# Zoom_camera.net
KiCad netlist of a schematic drawn in Altium Designer
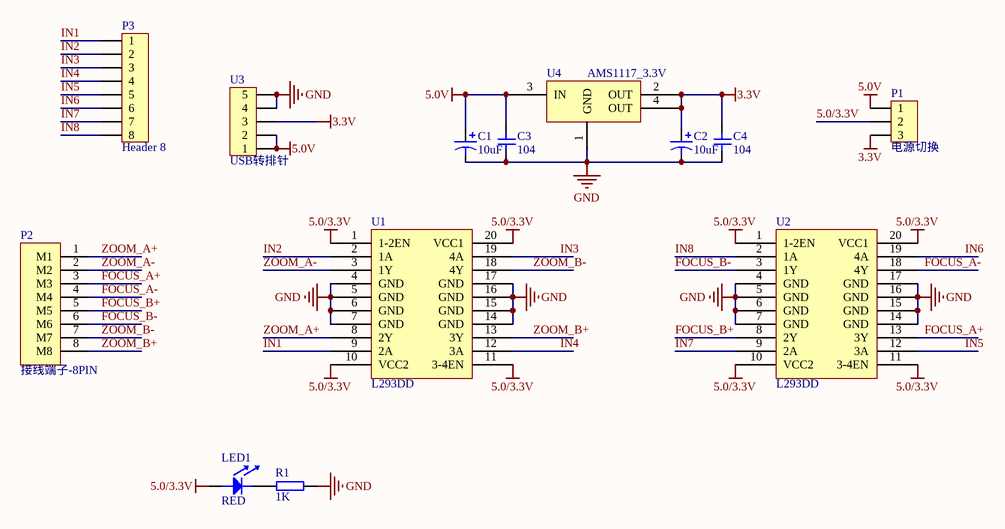
[diagram p0: Zoom_camera.SchDoc]

(export (version "E")
  (design (tool "Eeschema 10.0.6"))
  (components
    (comp (ref "C1")
      (value "10uF")
      (footprint "TAJ-B")
      (description "极性贴片电容")
      (libsource (lib "集大电协1.1.0") (part "Pol Cap"))
    )
    (comp (ref "C2")
      (value "10uF")
      (footprint "TAJ-B")
      (description "极性贴片电容")
      (libsource (lib "集大电协1.1.0") (part "Pol Cap"))
    )
    (comp (ref "C3")
      (value "104")
      (footprint "0805C")
      (description "无极贴片电容")
      (libsource (lib "集大电协1.1.0") (part "Cap1"))
    )
    (comp (ref "C4")
      (value "104")
      (footprint "0805C")
      (description "无极贴片电容")
      (libsource (lib "集大电协1.1.0") (part "Cap1"))
    )
    (comp (ref "LED1")
      (value "RED")
      (footprint "0805LED")
      (description "发光二极管")
      (libsource (lib "集大电协1.1.2") (part "LED"))
    )
    (comp (ref "P1")
      (value "电源切换")
      (footprint "Header 3")
      (description "排针")
      (libsource (lib "集大电协1.1.0") (part "Header 3"))
    )
    (comp (ref "P2")
      (value "接线端子-8PIN")
      (footprint "MX1.25MM-8P")
      (libsource (lib "集大电协1.1.0") (part "接线端子-8PIN"))
    )
    (comp (ref "P3")
      (value "Header 8")
      (footprint "Header 8")
      (description "排针")
      (libsource (lib "集大电协1.1.0") (part "Header 8"))
    )
    (comp (ref "R1")
      (value "1K")
      (footprint "0805R")
      (description "电阻")
      (libsource (lib "集大电协1.1.2") (part "Res"))
    )
    (comp (ref "U1") (value "L293DD") (footprint "SOP-20M") (libsource (lib "集大电协1.1.2") (part "L293D")))
    (comp (ref "U2") (value "L293DD") (footprint "SOP-20M") (libsource (lib "集大电协1.1.2") (part "L293D")))
    (comp (ref "U3") (value "USB转排针") (footprint "USB转排针") (libsource (lib "集大电协1.1.0") (part "USB转排针")))
    (comp (ref "U4")
      (value "AMS1117_3.3V")
      (footprint "SOT-223")
      (description "电源芯片")
      (libsource (lib "集大电协1.1.0") (part "AMS1117-3.3V/5.0V"))
    )
  )
  (nets
    (net (code "1") (name "/FOCUS_A+") (class "Default")
      (node (ref "P2") (pin "3") (pinfunction "M3_3") (pintype "passive"))
      (node (ref "U2") (pin "13") (pinfunction "3Y_13") (pintype "passive"))
    )
    (net (code "2") (name "/FOCUS_A-") (class "Default")
      (node (ref "P2") (pin "4") (pinfunction "M4_4") (pintype "passive"))
      (node (ref "U2") (pin "18") (pinfunction "4Y_18") (pintype "passive"))
    )
    (net (code "3") (name "/FOCUS_B+") (class "Default")
      (node (ref "P2") (pin "5") (pinfunction "M5_5") (pintype "passive"))
      (node (ref "U2") (pin "8") (pinfunction "2Y_8") (pintype "passive"))
    )
    (net (code "4") (name "/FOCUS_B-") (class "Default")
      (node (ref "P2") (pin "6") (pinfunction "M6_6") (pintype "passive"))
      (node (ref "U2") (pin "3") (pinfunction "1Y_3") (pintype "passive"))
    )
    (net (code "5") (name "/IN1") (class "Default")
      (node (ref "P3") (pin "1") (pinfunction "1_1") (pintype "passive"))
      (node (ref "U1") (pin "9") (pinfunction "2A_9") (pintype "passive"))
    )
    (net (code "6") (name "/IN2") (class "Default")
      (node (ref "P3") (pin "2") (pinfunction "2_2") (pintype "passive"))
      (node (ref "U1") (pin "2") (pinfunction "1A_2") (pintype "passive"))
    )
    (net (code "7") (name "/IN3") (class "Default")
      (node (ref "P3") (pin "3") (pinfunction "3_3") (pintype "passive"))
      (node (ref "U1") (pin "19") (pinfunction "4A_19") (pintype "passive"))
    )
    (net (code "8") (name "/IN4") (class "Default")
      (node (ref "P3") (pin "4") (pinfunction "4_4") (pintype "passive"))
      (node (ref "U1") (pin "12") (pinfunction "3A_12") (pintype "passive"))
    )
    (net (code "9") (name "/IN5") (class "Default")
      (node (ref "P3") (pin "5") (pinfunction "5_5") (pintype "passive"))
      (node (ref "U2") (pin "12") (pinfunction "3A_12") (pintype "passive"))
    )
    (net (code "10") (name "/IN6") (class "Default")
      (node (ref "P3") (pin "6") (pinfunction "6_6") (pintype "passive"))
      (node (ref "U2") (pin "19") (pinfunction "4A_19") (pintype "passive"))
    )
    (net (code "11") (name "/IN7") (class "Default")
      (node (ref "P3") (pin "7") (pinfunction "7_7") (pintype "passive"))
      (node (ref "U2") (pin "9") (pinfunction "2A_9") (pintype "passive"))
    )
    (net (code "12") (name "/IN8") (class "Default")
      (node (ref "P3") (pin "8") (pinfunction "8_8") (pintype "passive"))
      (node (ref "U2") (pin "2") (pinfunction "1A_2") (pintype "passive"))
    )
    (net (code "13") (name "/ZOOM_A+") (class "Default")
      (node (ref "P2") (pin "1") (pinfunction "M1_1") (pintype "passive"))
      (node (ref "U1") (pin "8") (pinfunction "2Y_8") (pintype "passive"))
    )
    (net (code "14") (name "/ZOOM_A-") (class "Default")
      (node (ref "P2") (pin "2") (pinfunction "M2_2") (pintype "passive"))
      (node (ref "U1") (pin "3") (pinfunction "1Y_3") (pintype "passive"))
    )
    (net (code "15") (name "/ZOOM_B+") (class "Default")
      (node (ref "P2") (pin "8") (pinfunction "M8_8") (pintype "passive"))
      (node (ref "U1") (pin "13") (pinfunction "3Y_13") (pintype "passive"))
    )
    (net (code "16") (name "/ZOOM_B-") (class "Default")
      (node (ref "P2") (pin "7") (pinfunction "M7_7") (pintype "passive"))
      (node (ref "U1") (pin "18") (pinfunction "4Y_18") (pintype "passive"))
    )
    (net (code "17") (name "3.3V") (class "Default")
      (node (ref "C2") (pin "1") (pinfunction "1_1") (pintype "passive"))
      (node (ref "C4") (pin "2") (pinfunction "2_2") (pintype "passive"))
      (node (ref "P1") (pin "3") (pinfunction "3_3") (pintype "passive"))
      (node (ref "U3") (pin "3") (pinfunction "3_3") (pintype "passive"))
      (node (ref "U4") (pin "2") (pinfunction "OUT_2") (pintype "passive"))
      (node (ref "U4") (pin "4") (pinfunction "OUT_4") (pintype "passive"))
    )
    (net (code "18") (name "5.0V") (class "Default")
      (node (ref "C1") (pin "1") (pinfunction "1_1") (pintype "passive"))
      (node (ref "C3") (pin "2") (pinfunction "2_2") (pintype "passive"))
      (node (ref "P1") (pin "1") (pinfunction "1_1") (pintype "passive"))
      (node (ref "U3") (pin "1") (pinfunction "1_1") (pintype "passive"))
      (node (ref "U3") (pin "2") (pinfunction "2_2") (pintype "passive"))
      (node (ref "U4") (pin "3") (pinfunction "IN_3") (pintype "passive"))
    )
    (net (code "19") (name "5.0{slash}3.3V") (class "Default")
      (node (ref "LED1") (pin "1") (pintype "passive"))
      (node (ref "P1") (pin "2") (pinfunction "2_2") (pintype "passive"))
      (node (ref "U1") (pin "1") (pinfunction "1-2EN_1") (pintype "passive"))
      (node (ref "U1") (pin "10") (pinfunction "VCC2_10") (pintype "passive"))
      (node (ref "U1") (pin "11") (pinfunction "3-4EN_11") (pintype "passive"))
      (node (ref "U1") (pin "20") (pinfunction "VCC1_20") (pintype "passive"))
      (node (ref "U2") (pin "1") (pinfunction "1-2EN_1") (pintype "passive"))
      (node (ref "U2") (pin "10") (pinfunction "VCC2_10") (pintype "passive"))
      (node (ref "U2") (pin "11") (pinfunction "3-4EN_11") (pintype "passive"))
      (node (ref "U2") (pin "20") (pinfunction "VCC1_20") (pintype "passive"))
    )
    (net (code "20") (name "GND") (class "Default")
      (node (ref "C1") (pin "2") (pinfunction "2_2") (pintype "passive"))
      (node (ref "C2") (pin "2") (pinfunction "2_2") (pintype "passive"))
      (node (ref "C3") (pin "1") (pinfunction "1_1") (pintype "passive"))
      (node (ref "C4") (pin "1") (pinfunction "1_1") (pintype "passive"))
      (node (ref "R1") (pin "2") (pinfunction "2_2") (pintype "passive"))
      (node (ref "U1") (pin "14") (pinfunction "GND_14") (pintype "passive"))
      (node (ref "U1") (pin "15") (pinfunction "GND_15") (pintype "passive"))
      (node (ref "U1") (pin "16") (pinfunction "GND_16") (pintype "passive"))
      (node (ref "U1") (pin "17") (pinfunction "GND_17") (pintype "passive"))
      (node (ref "U1") (pin "4") (pinfunction "GND_4") (pintype "passive"))
      (node (ref "U1") (pin "5") (pinfunction "GND_5") (pintype "passive"))
      (node (ref "U1") (pin "6") (pinfunction "GND_6") (pintype "passive"))
      (node (ref "U1") (pin "7") (pinfunction "GND_7") (pintype "passive"))
      (node (ref "U2") (pin "14") (pinfunction "GND_14") (pintype "passive"))
      (node (ref "U2") (pin "15") (pinfunction "GND_15") (pintype "passive"))
      (node (ref "U2") (pin "16") (pinfunction "GND_16") (pintype "passive"))
      (node (ref "U2") (pin "17") (pinfunction "GND_17") (pintype "passive"))
      (node (ref "U2") (pin "4") (pinfunction "GND_4") (pintype "passive"))
      (node (ref "U2") (pin "5") (pinfunction "GND_5") (pintype "passive"))
      (node (ref "U2") (pin "6") (pinfunction "GND_6") (pintype "passive"))
      (node (ref "U2") (pin "7") (pinfunction "GND_7") (pintype "passive"))
      (node (ref "U3") (pin "4") (pinfunction "4_4") (pintype "passive"))
      (node (ref "U3") (pin "5") (pinfunction "5_5") (pintype "passive"))
      (node (ref "U4") (pin "1") (pinfunction "GND_1") (pintype "passive"))
    )
    (net (code "21") (name "Net-(LED1-Pad2)") (class "Default")
      (node (ref "LED1") (pin "2") (pinfunction "2_2") (pintype "passive"))
      (node (ref "R1") (pin "1") (pinfunction "1_1") (pintype "passive"))
    )
  )
)
